# piezo-preamp-tickler_V2-RevB_REMOTE_7081.net
KiCad netlist of a schematic drawn in EAGLE
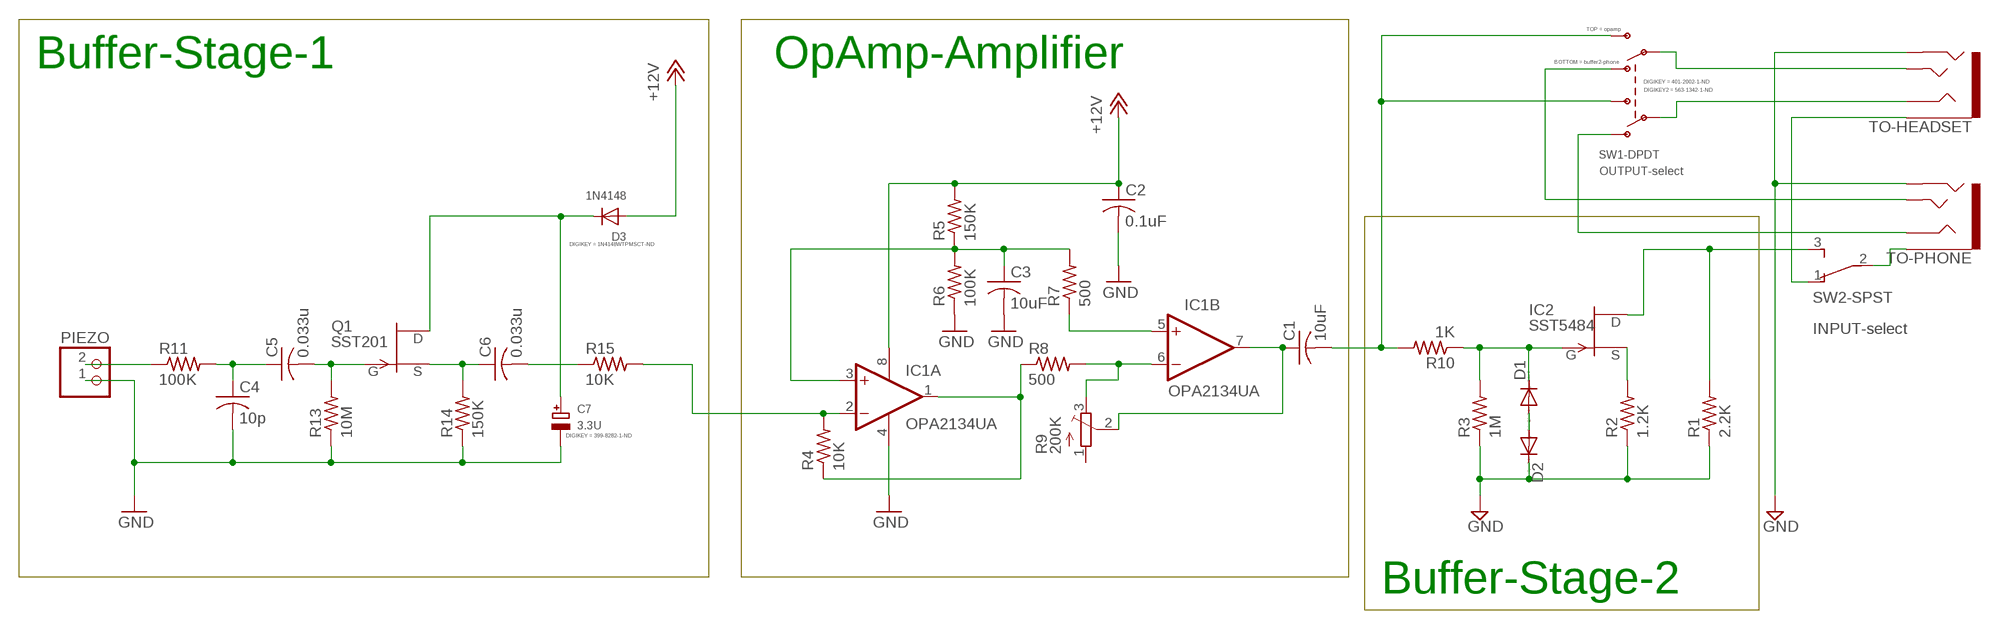
[diagram p0: schematic, sheet 1]
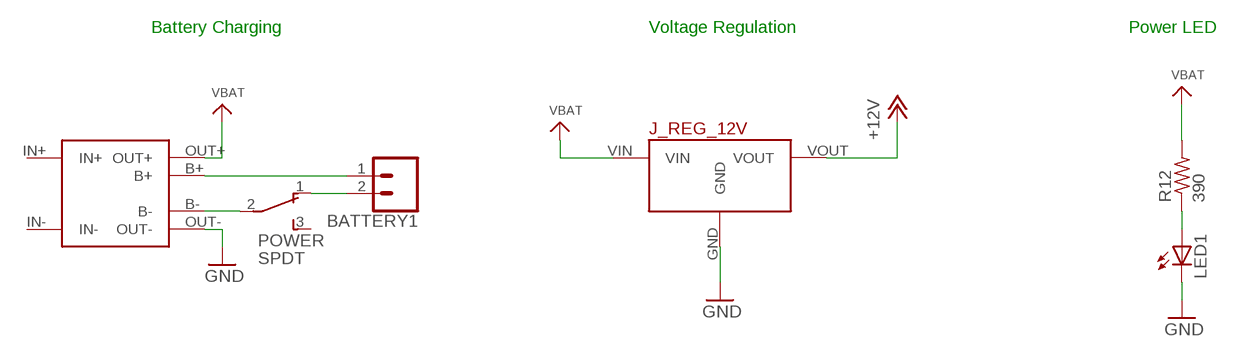
[diagram p1: schematic, sheet 2]

(export (version "E")
  (design (tool "Eeschema 10.0.6"))
  (components
    (comp (ref "BATTERY1")
      (value "CONN_02LOCK")
      (footprint "eagle-import:1X02_LOCK")
      (libsource (lib "eagle-import") (part "CONN_02LOCK"))
    )
    (comp (ref "J_REG_12V")
      (value "POLOLU_VOLTAGE_REGULATORS_3PIN")
      (footprint "eagle-import:POLOLU_5V-12V_STEPUP_U3V12F5-U3V12F12")
      (libsource (lib "eagle-import") (part "POLOLU_VOLTAGE_REGULATORS_3PIN"))
    )
    (comp (ref "LED1")
      (value "LED3MM")
      (footprint "eagle-import:LED3MM")
      (libsource (lib "eagle-import") (part "LED3MM"))
    )
    (comp (ref "POWER")
      (value "SPDT")
      (footprint "eagle-import:SWITCH_SPDT-TE-CONNECT")
      (libsource (lib "eagle-import") (part "SWITCH_SPDTTE-CONNECT"))
    )
    (comp (ref "R12")
      (value "390")
      (footprint "eagle-import:R0805")
      (libsource (lib "eagle-import") (part "R-US_R0805"))
    )
    (comp (ref "USB-LIPO-CHARGER")
      (value "TP4056-MODULE")
      (footprint "eagle-import:TP4056-LITHIUM-PROTECTED-MODULE")
      (libsource (lib "eagle-import") (part "TP4056-MODULE"))
    )
    (comp (ref "C1")
      (value "10uF")
      (footprint "eagle-import:C0805K")
      (libsource (lib "eagle-import") (part "C-USC0805K"))
    )
    (comp (ref "C2")
      (value "0.1uF")
      (footprint "eagle-import:C0805K")
      (libsource (lib "eagle-import") (part "C-USC0805K"))
    )
    (comp (ref "C3")
      (value "10uF")
      (footprint "eagle-import:C0805K")
      (libsource (lib "eagle-import") (part "C-USC0805K"))
    )
    (comp (ref "C4")
      (value "10p")
      (footprint "eagle-import:C0805K")
      (libsource (lib "eagle-import") (part "C-USC0805K"))
    )
    (comp (ref "C5")
      (value "0.033u")
      (footprint "eagle-import:C0805K")
      (libsource (lib "eagle-import") (part "C-USC0805K"))
    )
    (comp (ref "C6")
      (value "0.033u")
      (footprint "eagle-import:C0805K")
      (libsource (lib "eagle-import") (part "C-USC0805K"))
    )
    (comp (ref "C7")
      (value "3.3U")
      (footprint "eagle-import:EIA3216-18_A-R")
      (fields (field (name "DIGIKEY") "399-8282-1-ND"))
      (libsource (lib "eagle-import") (part "CAP_TANTALUMA/3216_REFLOW"))
    )
    (comp (ref "D1")
      (value "DIODE-SOD123")
      (footprint "eagle-import:SOD123")
      (libsource (lib "eagle-import") (part "DIODE-SOD123"))
    )
    (comp (ref "D2")
      (value "DIODE-SOD123")
      (footprint "eagle-import:SOD123")
      (libsource (lib "eagle-import") (part "DIODE-SOD123"))
    )
    (comp (ref "D3")
      (value "1N4148")
      (footprint "eagle-import:SOD-123")
      (fields (field (name "DIGIKEY") "1N4148WTPMSCT-ND"))
      (libsource (lib "eagle-import") (part "DIODESOD-123"))
    )
    (comp (ref "IC1")
      (value "OPA2134UA")
      (footprint "eagle-import:SO08")
      (libsource (lib "eagle-import") (part "OPA2UA134"))
    )
    (comp (ref "IC2")
      (value "SST5484")
      (footprint "eagle-import:SOT23")
      (libsource (lib "eagle-import") (part "?548SST4"))
    )
    (comp (ref "PIEZO")
      (value "JST_2PIN-THM")
      (footprint "eagle-import:JST-PH-2-THM")
      (libsource (lib "eagle-import") (part "JST_2PIN-THM"))
    )
    (comp (ref "Q1")
      (value "SST201")
      (footprint "eagle-import:SOT23")
      (libsource (lib "eagle-import") (part "?20SST1"))
    )
    (comp (ref "R1")
      (value "2.2K")
      (footprint "eagle-import:R0603")
      (libsource (lib "eagle-import") (part "R-US_R0603"))
    )
    (comp (ref "R2")
      (value "1.2K")
      (footprint "eagle-import:R0603")
      (libsource (lib "eagle-import") (part "R-US_R0603"))
    )
    (comp (ref "R3")
      (value "1M")
      (footprint "eagle-import:R0603")
      (libsource (lib "eagle-import") (part "R-US_R0603"))
    )
    (comp (ref "R4")
      (value "10K")
      (footprint "eagle-import:R0603")
      (libsource (lib "eagle-import") (part "R-US_R0603"))
    )
    (comp (ref "R5")
      (value "150K")
      (footprint "eagle-import:R0603")
      (libsource (lib "eagle-import") (part "R-US_R0603"))
    )
    (comp (ref "R6")
      (value "100K")
      (footprint "eagle-import:R0603")
      (libsource (lib "eagle-import") (part "R-US_R0603"))
    )
    (comp (ref "R7")
      (value "500")
      (footprint "eagle-import:R0603")
      (libsource (lib "eagle-import") (part "R-US_R0603"))
    )
    (comp (ref "R8")
      (value "500")
      (footprint "eagle-import:R0603")
      (libsource (lib "eagle-import") (part "R-US_R0603"))
    )
    (comp (ref "R9")
      (value "200K")
      (footprint "eagle-import:TC33X")
      (libsource (lib "eagle-import") (part "TRIMPOTTC33X"))
    )
    (comp (ref "R10")
      (value "1K")
      (footprint "eagle-import:R0603")
      (libsource (lib "eagle-import") (part "R-US_R0603"))
    )
    (comp (ref "R11")
      (value "100K")
      (footprint "eagle-import:R0603")
      (libsource (lib "eagle-import") (part "R-US_R0603"))
    )
    (comp (ref "R13")
      (value "10M")
      (footprint "eagle-import:R0603")
      (libsource (lib "eagle-import") (part "R-US_R0603"))
    )
    (comp (ref "R14")
      (value "150K")
      (footprint "eagle-import:R0603")
      (libsource (lib "eagle-import") (part "R-US_R0603"))
    )
    (comp (ref "R15")
      (value "10K")
      (footprint "eagle-import:R0603")
      (libsource (lib "eagle-import") (part "R-US_R0603"))
    )
    (comp (ref "SW1-DPDT")
      (value "OUTPUT-select")
      (footprint "eagle-import:DPDT_SMT_JS202011SCQN")
      (fields
        (field (name "BOTTOM") "buffer2-phone")
        (field (name "DIGIKEY") "401-2002-1-ND")
        (field (name "DIGIKEY2") "563-1342-1-ND")
        (field (name "TOP") "opamp")
      )
      (libsource (lib "eagle-import") (part "SWITCH_DPDT"))
    )
    (comp (ref "SW2-SPST")
      (value "INPUT-select")
      (footprint "eagle-import:SWITCH_SPDT-TE-CONNECT")
      (libsource (lib "eagle-import") (part "SWITCH_SPDTTE-CONNECT"))
    )
    (comp (ref "TO-HEADSET")
      (value "AUDIO-JACK3LGPADS")
      (footprint "eagle-import:AUDIO-JACK-TRRS-SMD")
      (libsource (lib "eagle-import") (part "AUDIO-JACK3LGPADS"))
    )
    (comp (ref "TO-PHONE")
      (value "AUDIO-JACK3LGPADS")
      (footprint "eagle-import:AUDIO-JACK-TRRS-SMD")
      (libsource (lib "eagle-import") (part "AUDIO-JACK3LGPADS"))
    )
  )
  (nets
    (net (code "1") (name "+12V") (class "Default")
      (node (ref "C2") (pin "1") (pinfunction "1_1") (pintype "passive"))
      (node (ref "D3") (pin "A") (pinfunction "A_A") (pintype "passive"))
      (node (ref "IC1") (pin "8") (pinfunction "V+_8") (pintype "power_in"))
      (node (ref "J_REG_12V") (pin "VOUT") (pinfunction "VOUT_VOUT") (pintype "bidirectional"))
      (node (ref "R5") (pin "2") (pinfunction "2_2") (pintype "passive"))
    )
    (net (code "2") (name "GND") (class "Default")
      (node (ref "C2") (pin "2") (pinfunction "2_2") (pintype "passive"))
      (node (ref "C3") (pin "2") (pinfunction "2_2") (pintype "passive"))
      (node (ref "C4") (pin "2") (pinfunction "2_2") (pintype "passive"))
      (node (ref "C7") (pin "-") (pinfunction "-_-") (pintype "passive"))
      (node (ref "D2") (pin "C") (pinfunction "C_C") (pintype "passive"))
      (node (ref "IC1") (pin "4") (pinfunction "V-_4") (pintype "power_in"))
      (node (ref "J_REG_12V") (pin "GND") (pinfunction "GND_GND") (pintype "bidirectional"))
      (node (ref "LED1") (pin "K") (pinfunction "C_K") (pintype "passive"))
      (node (ref "PIEZO") (pin "1") (pinfunction "2_1") (pintype "passive"))
      (node (ref "R1") (pin "1") (pinfunction "1_1") (pintype "passive"))
      (node (ref "R13") (pin "1") (pinfunction "1_1") (pintype "passive"))
      (node (ref "R14") (pin "1") (pinfunction "1_1") (pintype "passive"))
      (node (ref "R2") (pin "1") (pinfunction "1_1") (pintype "passive"))
      (node (ref "R3") (pin "1") (pinfunction "1_1") (pintype "passive"))
      (node (ref "R6") (pin "1") (pinfunction "1_1") (pintype "passive"))
      (node (ref "TO-HEADSET") (pin "RING2") (pinfunction "RING2_RING2") (pintype "bidirectional"))
      (node (ref "TO-PHONE") (pin "RING2") (pinfunction "RING2_RING2") (pintype "bidirectional"))
      (node (ref "USB-LIPO-CHARGER") (pin "OUT-") (pinfunction "OUT-_OUT-") (pintype "power_in"))
    )
    (net (code "3") (name "IN+") (class "Default")
      (node (ref "USB-LIPO-CHARGER") (pin "IN+") (pinfunction "IN+_IN+") (pintype "power_in"))
    )
    (net (code "4") (name "IN-") (class "Default")
      (node (ref "USB-LIPO-CHARGER") (pin "IN-") (pinfunction "IN-_IN-") (pintype "power_in"))
    )
    (net (code "5") (name "Net-(BATTERY1-Pad1)") (class "Default")
      (node (ref "BATTERY1") (pin "1") (pinfunction "1_1") (pintype "passive"))
      (node (ref "USB-LIPO-CHARGER") (pin "B+") (pinfunction "B+_B+") (pintype "power_in"))
    )
    (net (code "6") (name "Net-(BATTERY1-Pad2)") (class "Default")
      (node (ref "BATTERY1") (pin "2") (pinfunction "2_2") (pintype "passive"))
      (node (ref "POWER") (pin "1") (pinfunction "1_1") (pintype "passive"))
    )
    (net (code "7") (name "Net-(C4-Pad1)") (class "Default")
      (node (ref "C4") (pin "1") (pinfunction "1_1") (pintype "passive"))
      (node (ref "C5") (pin "1") (pinfunction "1_1") (pintype "passive"))
      (node (ref "R11") (pin "2") (pinfunction "2_2") (pintype "passive"))
    )
    (net (code "8") (name "Net-(C6-Pad2)") (class "Default")
      (node (ref "C6") (pin "2") (pinfunction "2_2") (pintype "passive"))
      (node (ref "R15") (pin "1") (pinfunction "1_1") (pintype "passive"))
    )
    (net (code "9") (name "Net-(D1-PadA)") (class "Default")
      (node (ref "D1") (pin "A") (pinfunction "A_A") (pintype "passive"))
      (node (ref "D2") (pin "A") (pinfunction "A_A") (pintype "passive"))
    )
    (net (code "10") (name "Net-(IC1A-+IN)") (class "Default")
      (node (ref "C3") (pin "1") (pinfunction "1_1") (pintype "passive"))
      (node (ref "IC1") (pin "3") (pinfunction "+IN_3") (pintype "input"))
      (node (ref "R5") (pin "1") (pinfunction "1_1") (pintype "passive"))
      (node (ref "R6") (pin "2") (pinfunction "2_2") (pintype "passive"))
      (node (ref "R7") (pin "2") (pinfunction "2_2") (pintype "passive"))
    )
    (net (code "11") (name "Net-(IC1A--IN)") (class "Default")
      (node (ref "IC1") (pin "2") (pinfunction "-IN_2") (pintype "input"))
      (node (ref "R15") (pin "2") (pinfunction "2_2") (pintype "passive"))
      (node (ref "R4") (pin "2") (pinfunction "2_2") (pintype "passive"))
    )
    (net (code "12") (name "Net-(IC1A-OUT)") (class "Default")
      (node (ref "IC1") (pin "1") (pinfunction "OUT_1") (pintype "output"))
      (node (ref "R4") (pin "1") (pinfunction "1_1") (pintype "passive"))
      (node (ref "R8") (pin "1") (pinfunction "1_1") (pintype "passive"))
    )
    (net (code "13") (name "Net-(IC1B-+IN)") (class "Default")
      (node (ref "IC1") (pin "5") (pinfunction "+IN_5") (pintype "input"))
      (node (ref "R7") (pin "1") (pinfunction "1_1") (pintype "passive"))
    )
    (net (code "14") (name "Net-(IC1B--IN)") (class "Default")
      (node (ref "IC1") (pin "6") (pinfunction "-IN_6") (pintype "input"))
      (node (ref "R8") (pin "2") (pinfunction "2_2") (pintype "passive"))
      (node (ref "R9") (pin "3") (pinfunction "E_3") (pintype "passive"))
    )
    (net (code "15") (name "Net-(IC1B-OUT)") (class "Default")
      (node (ref "C1") (pin "1") (pinfunction "1_1") (pintype "passive"))
      (node (ref "IC1") (pin "7") (pinfunction "OUT_7") (pintype "output"))
      (node (ref "R9") (pin "2") (pinfunction "S_2") (pintype "passive"))
    )
    (net (code "16") (name "Net-(IC2-D)") (class "Default")
      (node (ref "IC2") (pin "1") (pinfunction "D_1") (pintype "passive"))
      (node (ref "R1") (pin "2") (pinfunction "2_2") (pintype "passive"))
      (node (ref "SW2-SPST") (pin "3") (pinfunction "3_3") (pintype "passive"))
    )
    (net (code "17") (name "Net-(IC2-G)") (class "Default")
      (node (ref "D1") (pin "C") (pinfunction "C_C") (pintype "passive"))
      (node (ref "IC2") (pin "3") (pinfunction "G_3") (pintype "passive"))
      (node (ref "R10") (pin "1") (pinfunction "1_1") (pintype "passive"))
      (node (ref "R3") (pin "2") (pinfunction "2_2") (pintype "passive"))
    )
    (net (code "18") (name "Net-(IC2-S)") (class "Default")
      (node (ref "IC2") (pin "2") (pinfunction "S_2") (pintype "passive"))
      (node (ref "R2") (pin "2") (pinfunction "2_2") (pintype "passive"))
    )
    (net (code "19") (name "Net-(LED1-PadA)") (class "Default")
      (node (ref "LED1") (pin "A") (pinfunction "A_A") (pintype "passive"))
      (node (ref "R12") (pin "1") (pinfunction "1_1") (pintype "passive"))
    )
    (net (code "20") (name "Net-(PIEZO-1)") (class "Default")
      (node (ref "PIEZO") (pin "2") (pinfunction "1_2") (pintype "passive"))
      (node (ref "R11") (pin "1") (pinfunction "1_1") (pintype "passive"))
    )
    (net (code "21") (name "Net-(POWER-Pad2)") (class "Default")
      (node (ref "POWER") (pin "2") (pinfunction "2_2") (pintype "passive"))
      (node (ref "USB-LIPO-CHARGER") (pin "B-") (pinfunction "B-_B-") (pintype "power_in"))
    )
    (net (code "22") (name "Net-(Q1-D)") (class "Default")
      (node (ref "C7") (pin "+") (pinfunction "+_+") (pintype "passive"))
      (node (ref "D3") (pin "C") (pinfunction "C_C") (pintype "passive"))
      (node (ref "Q1") (pin "1") (pinfunction "D_1") (pintype "passive"))
    )
    (net (code "23") (name "Net-(Q1-G)") (class "Default")
      (node (ref "C5") (pin "2") (pinfunction "2_2") (pintype "passive"))
      (node (ref "Q1") (pin "3") (pinfunction "G_3") (pintype "passive"))
      (node (ref "R13") (pin "2") (pinfunction "2_2") (pintype "passive"))
    )
    (net (code "24") (name "Net-(Q1-S)") (class "Default")
      (node (ref "C6") (pin "1") (pinfunction "1_1") (pintype "passive"))
      (node (ref "Q1") (pin "2") (pinfunction "S_2") (pintype "passive"))
      (node (ref "R14") (pin "2") (pinfunction "2_2") (pintype "passive"))
    )
    (net (code "25") (name "Net-(SW1-DPDT-O1)") (class "Default")
      (node (ref "SW1-DPDT") (pin "P$1") (pinfunction "O1_P$1") (pintype "passive"))
      (node (ref "TO-PHONE") (pin "RING1") (pinfunction "RING1_RING1") (pintype "bidirectional"))
    )
    (net (code "26") (name "Net-(SW1-DPDT-O2)") (class "Default")
      (node (ref "SW1-DPDT") (pin "P$6") (pinfunction "O2_P$6") (pintype "passive"))
      (node (ref "TO-PHONE") (pin "TIP") (pinfunction "TIP_TIP") (pintype "bidirectional"))
    )
    (net (code "27") (name "Net-(SW1-DPDT-P1)") (class "Default")
      (node (ref "SW1-DPDT") (pin "P$2") (pinfunction "P1_P$2") (pintype "passive"))
      (node (ref "TO-HEADSET") (pin "RING1") (pinfunction "RING1_RING1") (pintype "bidirectional"))
    )
    (net (code "28") (name "Net-(SW1-DPDT-P2)") (class "Default")
      (node (ref "SW1-DPDT") (pin "P$5") (pinfunction "P2_P$5") (pintype "passive"))
      (node (ref "TO-HEADSET") (pin "TIP") (pinfunction "TIP_TIP") (pintype "bidirectional"))
    )
    (net (code "29") (name "Net-(SW1-DPDT-S1)") (class "Default")
      (node (ref "C1") (pin "2") (pinfunction "2_2") (pintype "passive"))
      (node (ref "R10") (pin "2") (pinfunction "2_2") (pintype "passive"))
      (node (ref "SW1-DPDT") (pin "P$3") (pinfunction "S1_P$3") (pintype "passive"))
      (node (ref "SW1-DPDT") (pin "P$4") (pinfunction "S2_P$4") (pintype "passive"))
    )
    (net (code "30") (name "Net-(SW2-SPST-Pad1)") (class "Default")
      (node (ref "SW2-SPST") (pin "1") (pinfunction "1_1") (pintype "passive"))
      (node (ref "TO-HEADSET") (pin "EARTH") (pinfunction "EARTH_EARTH") (pintype "bidirectional"))
    )
    (net (code "31") (name "Net-(SW2-SPST-Pad2)") (class "Default")
      (node (ref "SW2-SPST") (pin "2") (pinfunction "2_2") (pintype "passive"))
      (node (ref "TO-PHONE") (pin "EARTH") (pinfunction "EARTH_EARTH") (pintype "bidirectional"))
    )
    (net (code "32") (name "VBAT") (class "Default")
      (node (ref "J_REG_12V") (pin "VIN") (pinfunction "VIN_VIN") (pintype "bidirectional"))
      (node (ref "R12") (pin "2") (pinfunction "2_2") (pintype "passive"))
      (node (ref "USB-LIPO-CHARGER") (pin "OUT+") (pinfunction "OUT+_OUT+") (pintype "power_in"))
    )
    (net (code "33") (name "unconnected-(POWER-Pad3)") (class "Default")
      (node (ref "POWER") (pin "3") (pinfunction "3_3") (pintype "passive"))
    )
    (net (code "34") (name "unconnected-(R9-A-Pad1)") (class "Default")
      (node (ref "R9") (pin "1") (pinfunction "A_1") (pintype "passive"))
    )
  )
)
